# cry_gold.net
KiCad netlist of a schematic drawn in EAGLE
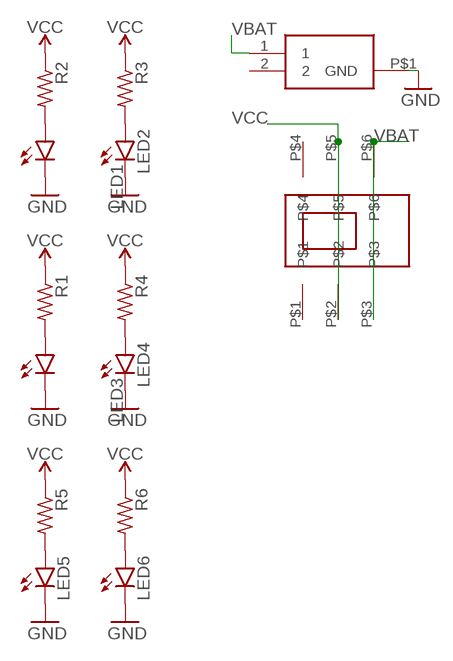
[diagram p0: schematic, sheet 1]

(export (version "E")
  (design (tool "Eeschema 10.0.6"))
  (components
    (comp (ref "LED1")
      (value "LEDCHIP-LED0805")
      (footprint "eagle-import:CHIP-LED0805")
      (libsource (lib "eagle-import") (part "LEDCHIP-LED0805"))
    )
    (comp (ref "LED2")
      (value "LEDCHIP-LED0805")
      (footprint "eagle-import:CHIP-LED0805")
      (libsource (lib "eagle-import") (part "LEDCHIP-LED0805"))
    )
    (comp (ref "LED3")
      (value "LEDCHIP-LED0805")
      (footprint "eagle-import:CHIP-LED0805")
      (libsource (lib "eagle-import") (part "LEDCHIP-LED0805"))
    )
    (comp (ref "LED4")
      (value "LEDCHIP-LED0805")
      (footprint "eagle-import:CHIP-LED0805")
      (libsource (lib "eagle-import") (part "LEDCHIP-LED0805"))
    )
    (comp (ref "LED5")
      (value "LEDCHIP-LED0805")
      (footprint "eagle-import:CHIP-LED0805")
      (libsource (lib "eagle-import") (part "LEDCHIP-LED0805"))
    )
    (comp (ref "LED6")
      (value "LEDCHIP-LED0805")
      (footprint "eagle-import:CHIP-LED0805")
      (libsource (lib "eagle-import") (part "LEDCHIP-LED0805"))
    )
    (comp (ref "R1")
      (value "R-US_R0603")
      (footprint "eagle-import:R0603")
      (libsource (lib "eagle-import") (part "R-US_R0603"))
    )
    (comp (ref "R2")
      (value "R-US_R0603")
      (footprint "eagle-import:R0603")
      (libsource (lib "eagle-import") (part "R-US_R0603"))
    )
    (comp (ref "R3")
      (value "R-US_R0603")
      (footprint "eagle-import:R0603")
      (libsource (lib "eagle-import") (part "R-US_R0603"))
    )
    (comp (ref "R4")
      (value "R-US_R0603")
      (footprint "eagle-import:R0603")
      (libsource (lib "eagle-import") (part "R-US_R0603"))
    )
    (comp (ref "R5")
      (value "R-US_R0603")
      (footprint "eagle-import:R0603")
      (libsource (lib "eagle-import") (part "R-US_R0603"))
    )
    (comp (ref "R6")
      (value "R-US_R0603")
      (footprint "eagle-import:R0603")
      (libsource (lib "eagle-import") (part "R-US_R0603"))
    )
    (comp (ref "U$1")
      (value "CL-SB-22A-02T-SLIDE-SWITCH-TUCKED-PADS")
      (footprint "eagle-import:CL-SB-22A-02T-DPDT-COMPACT-SWITCH")
      (libsource (lib "eagle-import") (part "CL-SB-22A-02T-SLIDE-SWITCH-TUCKED-PADS"))
    )
    (comp (ref "VBAT")
      (value "BAT-HLD-012-SMT")
      (footprint "eagle-import:BATHLD012SMT")
      (fields (field (name "MOUSER_PART_NUMBER") "712-BAT-HLD-012-SMT"))
      (libsource (lib "eagle-import") (part "BAT-HLD-012-SMT"))
    )
  )
  (nets
    (net (code "1") (name "/VBAT") (class "Default")
      (node (ref "U$1") (pin "P$3") (pinfunction "P$3_P$3") (pintype "bidirectional"))
      (node (ref "U$1") (pin "P$6") (pinfunction "P$6_P$6") (pintype "bidirectional"))
      (node (ref "VBAT") (pin "1") (pinfunction "1_1") (pintype "bidirectional"))
    )
    (net (code "2") (name "GND") (class "Default")
      (node (ref "LED1") (pin "C") (pinfunction "C_C") (pintype "passive"))
      (node (ref "LED2") (pin "C") (pinfunction "C_C") (pintype "passive"))
      (node (ref "LED3") (pin "C") (pinfunction "C_C") (pintype "passive"))
      (node (ref "LED4") (pin "C") (pinfunction "C_C") (pintype "passive"))
      (node (ref "LED5") (pin "C") (pinfunction "C_C") (pintype "passive"))
      (node (ref "LED6") (pin "C") (pinfunction "C_C") (pintype "passive"))
      (node (ref "VBAT") (pin "P$1") (pinfunction "GND_P$1") (pintype "bidirectional"))
    )
    (net (code "3") (name "Net-(LED1-PadA)") (class "Default")
      (node (ref "LED1") (pin "A") (pinfunction "A_A") (pintype "passive"))
      (node (ref "R2") (pin "2") (pinfunction "2_2") (pintype "passive"))
    )
    (net (code "4") (name "Net-(LED2-PadA)") (class "Default")
      (node (ref "LED2") (pin "A") (pinfunction "A_A") (pintype "passive"))
      (node (ref "R3") (pin "2") (pinfunction "2_2") (pintype "passive"))
    )
    (net (code "5") (name "Net-(LED3-PadA)") (class "Default")
      (node (ref "LED3") (pin "A") (pinfunction "A_A") (pintype "passive"))
      (node (ref "R1") (pin "2") (pinfunction "2_2") (pintype "passive"))
    )
    (net (code "6") (name "Net-(LED4-PadA)") (class "Default")
      (node (ref "LED4") (pin "A") (pinfunction "A_A") (pintype "passive"))
      (node (ref "R4") (pin "2") (pinfunction "2_2") (pintype "passive"))
    )
    (net (code "7") (name "Net-(LED5-PadA)") (class "Default")
      (node (ref "LED5") (pin "A") (pinfunction "A_A") (pintype "passive"))
      (node (ref "R5") (pin "2") (pinfunction "2_2") (pintype "passive"))
    )
    (net (code "8") (name "Net-(LED6-PadA)") (class "Default")
      (node (ref "LED6") (pin "A") (pinfunction "A_A") (pintype "passive"))
      (node (ref "R6") (pin "2") (pinfunction "2_2") (pintype "passive"))
    )
    (net (code "9") (name "VCC") (class "Default")
      (node (ref "R1") (pin "1") (pinfunction "1_1") (pintype "passive"))
      (node (ref "R2") (pin "1") (pinfunction "1_1") (pintype "passive"))
      (node (ref "R3") (pin "1") (pinfunction "1_1") (pintype "passive"))
      (node (ref "R4") (pin "1") (pinfunction "1_1") (pintype "passive"))
      (node (ref "R5") (pin "1") (pinfunction "1_1") (pintype "passive"))
      (node (ref "R6") (pin "1") (pinfunction "1_1") (pintype "passive"))
      (node (ref "U$1") (pin "P$2") (pinfunction "P$2_P$2") (pintype "bidirectional"))
      (node (ref "U$1") (pin "P$5") (pinfunction "P$5_P$5") (pintype "bidirectional"))
    )
    (net (code "10") (name "unconnected-(U$1-PadP$1)") (class "Default")
      (node (ref "U$1") (pin "P$1") (pinfunction "P$1_P$1") (pintype "bidirectional"))
    )
    (net (code "11") (name "unconnected-(U$1-PadP$4)") (class "Default")
      (node (ref "U$1") (pin "P$4") (pinfunction "P$4_P$4") (pintype "bidirectional"))
    )
    (net (code "12") (name "unconnected-(VBAT-Pad2)") (class "Default")
      (node (ref "VBAT") (pin "2") (pinfunction "2_2") (pintype "bidirectional"))
    )
  )
)
